# LCD_screen.net
KiCad netlist of a schematic drawn in Altium Designer
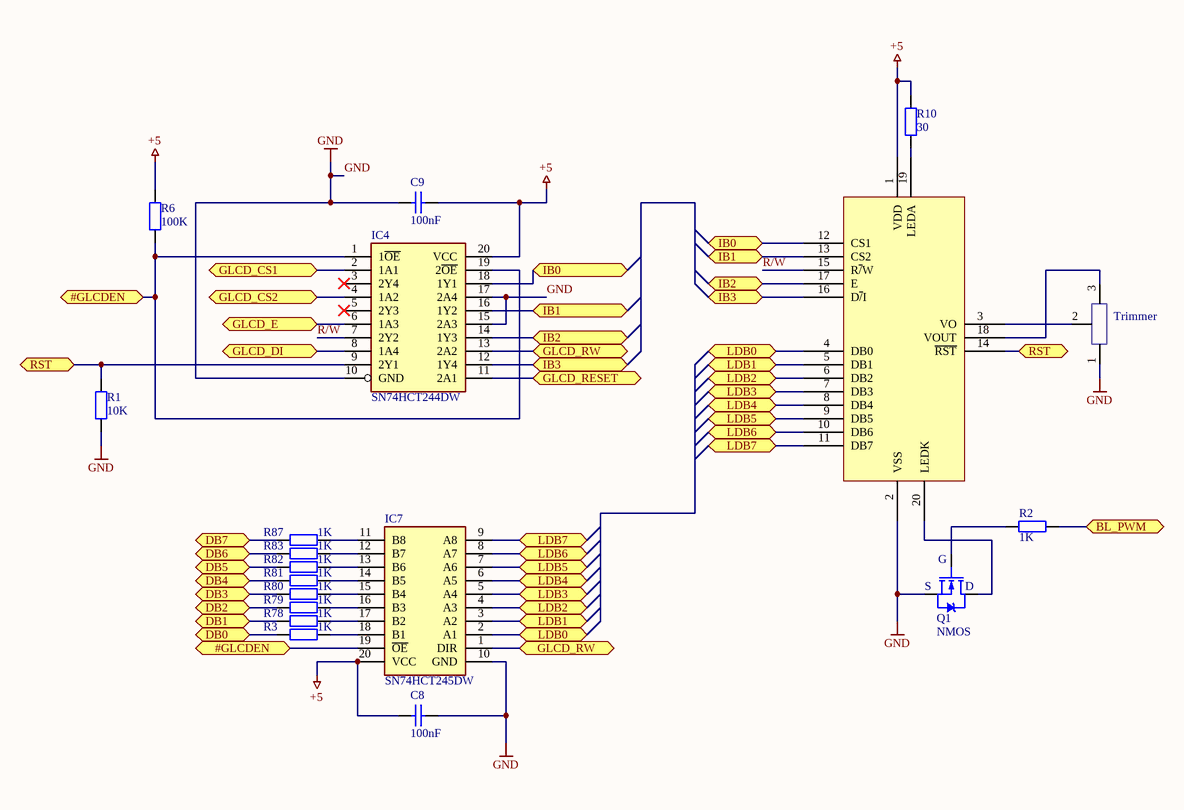
[diagram p0: LCD_screen.SchDoc]

(export (version "E")
  (design (tool "Eeschema 10.0.6"))
  (components
    (comp (ref "BC817")
      (value "LCD Screen")
      (footprint "FP_LCD")
      (libsource (lib "hallglib") (part "LCD Screen"))
    )
    (comp (ref "C8")
      (value "100nF")
      (footprint "FP_0805_CAP_085")
      (description "Capacitor")
      (libsource (lib "hallglib") (part "CAP"))
    )
    (comp (ref "C9")
      (value "100nF")
      (footprint "FP_0805_CAP_085")
      (description "Capacitor")
      (libsource (lib "hallglib") (part "CAP"))
    )
    (comp (ref "IC4")
      (value "SN74HCT244DW")
      (footprint "hallglib:SOIC127P1030X265-20N")
      (description "Integrated Circuit")
      (fields (field (name "MOUSER PART NUMBER") "595-SN74HCT244DW"))
      (libsource (lib "hallglib") (part "SN74HCT244DW"))
    )
    (comp (ref "IC7")
      (value "SN74HCT245DW")
      (footprint "hallglib:SOIC127P1030X265-20N")
      (description "Integrated Circuit")
      (fields (field (name "MOUSER PART NUMBER") "595-SN74HCT245DW"))
      (libsource (lib "hallglib") (part "SN74HCT245DW"))
    )
    (comp (ref "Q1")
      (value "NMOS")
      (footprint "FP_SOT23-3")
      (description "NXP - BSP030,115 - MOSFET, N CH, 30V, 10A, SOT223")
      (libsource (lib "hallglib") (part "NMOS"))
    )
    (comp (ref "R1")
      (value "10K")
      (footprint "FP_0805_RES")
      (description "Resistor")
      (libsource (lib "") (part "RES_1"))
    )
    (comp (ref "R2")
      (value "1K")
      (footprint "FP_0805_RES")
      (description "Resistor")
      (libsource (lib "hallglib") (part "RES"))
    )
    (comp (ref "R3")
      (value "1K")
      (footprint "FP_0805_RES")
      (description "Resistor")
      (libsource (lib "hallglib") (part "RES"))
    )
    (comp (ref "R6")
      (value "100K")
      (footprint "FP_0805_RES")
      (description "Resistor")
      (libsource (lib "") (part "RES_1"))
    )
    (comp (ref "R10")
      (value "30")
      (footprint "FP_0805_RES")
      (description "Resistor")
      (libsource (lib "") (part "RES_1"))
    )
    (comp (ref "R78")
      (value "1K")
      (footprint "FP_0805_RES")
      (description "Resistor")
      (libsource (lib "hallglib") (part "RES"))
    )
    (comp (ref "R79")
      (value "1K")
      (footprint "FP_0805_RES")
      (description "Resistor")
      (libsource (lib "hallglib") (part "RES"))
    )
    (comp (ref "R80")
      (value "1K")
      (footprint "FP_0805_RES")
      (description "Resistor")
      (libsource (lib "hallglib") (part "RES"))
    )
    (comp (ref "R81")
      (value "1K")
      (footprint "FP_0805_RES")
      (description "Resistor")
      (libsource (lib "hallglib") (part "RES"))
    )
    (comp (ref "R82")
      (value "1K")
      (footprint "FP_0805_RES")
      (description "Resistor")
      (libsource (lib "hallglib") (part "RES"))
    )
    (comp (ref "R83")
      (value "1K")
      (footprint "FP_0805_RES")
      (description "Resistor")
      (libsource (lib "hallglib") (part "RES"))
    )
    (comp (ref "R87")
      (value "1K")
      (footprint "FP_0805_RES")
      (description "Resistor")
      (libsource (lib "hallglib") (part "RES"))
    )
    (comp (ref "Trimmer")
      (value "~")
      (footprint "TRIM_3362P-1-502")
      (libsource (lib "hallglib") (part "Trimmer"))
    )
  )
  (nets
    (net (code "1") (name "+5") (class "Default")
      (node (ref "BC817") (pin "1") (pinfunction "VDD_1") (pintype "passive"))
      (node (ref "C8") (pin "1") (pinfunction "1_1") (pintype "passive"))
      (node (ref "C9") (pin "2") (pinfunction "2_2") (pintype "passive"))
      (node (ref "IC4") (pin "20") (pinfunction "VCC_20") (pintype "passive"))
      (node (ref "IC7") (pin "20") (pinfunction "VCC_20") (pintype "passive"))
      (node (ref "R10") (pin "2") (pinfunction "2_2") (pintype "passive"))
      (node (ref "R6") (pin "2") (pinfunction "2_2") (pintype "passive"))
    )
    (net (code "2") (name "/#GLCDEN") (class "Default")
      (node (ref "IC4") (pin "1") (pinfunction "1~{OE}_1") (pintype "passive"))
      (node (ref "IC4") (pin "19") (pinfunction "2~{OE}_19") (pintype "passive"))
      (node (ref "IC7") (pin "19") (pinfunction "~{OE}_19") (pintype "passive"))
      (node (ref "R6") (pin "1") (pinfunction "1_1") (pintype "passive"))
    )
    (net (code "3") (name "/BL_PWM") (class "Default")
      (node (ref "R2") (pin "2") (pinfunction "2_2") (pintype "passive"))
    )
    (net (code "4") (name "/DB0") (class "Default")
      (node (ref "R3") (pin "1") (pinfunction "1_1") (pintype "passive"))
    )
    (net (code "5") (name "/DB1") (class "Default")
      (node (ref "R78") (pin "1") (pinfunction "1_1") (pintype "passive"))
    )
    (net (code "6") (name "/DB2") (class "Default")
      (node (ref "R79") (pin "1") (pinfunction "1_1") (pintype "passive"))
    )
    (net (code "7") (name "/DB3") (class "Default")
      (node (ref "R80") (pin "1") (pinfunction "1_1") (pintype "passive"))
    )
    (net (code "8") (name "/DB4") (class "Default")
      (node (ref "R81") (pin "1") (pinfunction "1_1") (pintype "passive"))
    )
    (net (code "9") (name "/DB5") (class "Default")
      (node (ref "R82") (pin "1") (pinfunction "1_1") (pintype "passive"))
    )
    (net (code "10") (name "/DB6") (class "Default")
      (node (ref "R83") (pin "1") (pinfunction "1_1") (pintype "passive"))
    )
    (net (code "11") (name "/DB7") (class "Default")
      (node (ref "R87") (pin "1") (pinfunction "1_1") (pintype "passive"))
    )
    (net (code "12") (name "/GLCD_CS1") (class "Default")
      (node (ref "IC4") (pin "2") (pinfunction "1A1_2") (pintype "passive"))
    )
    (net (code "13") (name "/GLCD_CS2") (class "Default")
      (node (ref "IC4") (pin "4") (pinfunction "1A2_4") (pintype "passive"))
    )
    (net (code "14") (name "/GLCD_DI") (class "Default")
      (node (ref "IC4") (pin "8") (pinfunction "1A4_8") (pintype "passive"))
    )
    (net (code "15") (name "/GLCD_E") (class "Default")
      (node (ref "IC4") (pin "6") (pinfunction "1A3_6") (pintype "passive"))
    )
    (net (code "16") (name "/GLCD_RESET") (class "Default")
      (node (ref "IC4") (pin "11") (pinfunction "2A1_11") (pintype "passive"))
    )
    (net (code "17") (name "/GLCD_RW") (class "Default")
      (node (ref "IC4") (pin "13") (pinfunction "2A2_13") (pintype "passive"))
      (node (ref "IC7") (pin "1") (pinfunction "DIR_1") (pintype "passive"))
    )
    (net (code "18") (name "/IB0") (class "Default")
      (node (ref "BC817") (pin "12") (pinfunction "CS1_12") (pintype "passive"))
      (node (ref "IC4") (pin "18") (pinfunction "1Y1_18") (pintype "passive"))
    )
    (net (code "19") (name "/IB1") (class "Default")
      (node (ref "BC817") (pin "13") (pinfunction "CS2_13") (pintype "passive"))
      (node (ref "IC4") (pin "16") (pinfunction "1Y2_16") (pintype "passive"))
    )
    (net (code "20") (name "/IB2") (class "Default")
      (node (ref "BC817") (pin "17") (pinfunction "E_17") (pintype "passive"))
      (node (ref "IC4") (pin "14") (pinfunction "1Y3_14") (pintype "passive"))
    )
    (net (code "21") (name "/IB3") (class "Default")
      (node (ref "BC817") (pin "16") (pinfunction "D~{/}I_16") (pintype "passive"))
      (node (ref "IC4") (pin "12") (pinfunction "1Y4_12") (pintype "passive"))
    )
    (net (code "22") (name "/LDB0") (class "Default")
      (node (ref "BC817") (pin "4") (pinfunction "DB0_4") (pintype "passive"))
      (node (ref "IC7") (pin "2") (pinfunction "A1_2") (pintype "passive"))
    )
    (net (code "23") (name "/LDB1") (class "Default")
      (node (ref "BC817") (pin "5") (pinfunction "DB1_5") (pintype "passive"))
      (node (ref "IC7") (pin "3") (pinfunction "A2_3") (pintype "passive"))
    )
    (net (code "24") (name "/LDB2") (class "Default")
      (node (ref "BC817") (pin "6") (pinfunction "DB2_6") (pintype "passive"))
      (node (ref "IC7") (pin "4") (pinfunction "A3_4") (pintype "passive"))
    )
    (net (code "25") (name "/LDB3") (class "Default")
      (node (ref "BC817") (pin "7") (pinfunction "DB3_7") (pintype "passive"))
      (node (ref "IC7") (pin "5") (pinfunction "A4_5") (pintype "passive"))
    )
    (net (code "26") (name "/LDB4") (class "Default")
      (node (ref "BC817") (pin "8") (pinfunction "DB4_8") (pintype "passive"))
      (node (ref "IC7") (pin "6") (pinfunction "A5_6") (pintype "passive"))
    )
    (net (code "27") (name "/LDB5") (class "Default")
      (node (ref "BC817") (pin "9") (pinfunction "DB5_9") (pintype "passive"))
      (node (ref "IC7") (pin "7") (pinfunction "A6_7") (pintype "passive"))
    )
    (net (code "28") (name "/LDB6") (class "Default")
      (node (ref "BC817") (pin "10") (pinfunction "DB6_10") (pintype "passive"))
      (node (ref "IC7") (pin "8") (pinfunction "A7_8") (pintype "passive"))
    )
    (net (code "29") (name "/LDB7") (class "Default")
      (node (ref "BC817") (pin "11") (pinfunction "DB7_11") (pintype "passive"))
      (node (ref "IC7") (pin "9") (pinfunction "A8_9") (pintype "passive"))
    )
    (net (code "30") (name "/RST") (class "Default")
      (node (ref "BC817") (pin "14") (pinfunction "RST_14") (pintype "passive"))
      (node (ref "IC4") (pin "9") (pinfunction "2Y1_9") (pintype "passive"))
      (node (ref "R1") (pin "2") (pinfunction "2_2") (pintype "passive"))
    )
    (net (code "31") (name "/R{slash}W") (class "Default")
      (node (ref "BC817") (pin "15") (pinfunction "R~{/}W_15") (pintype "passive"))
      (node (ref "IC4") (pin "7") (pinfunction "2Y2_7") (pintype "passive"))
    )
    (net (code "32") (name "GND") (class "Default")
      (node (ref "BC817") (pin "2") (pinfunction "VSS_2") (pintype "passive"))
      (node (ref "C8") (pin "2") (pinfunction "2_2") (pintype "passive"))
      (node (ref "C9") (pin "1") (pinfunction "1_1") (pintype "passive"))
      (node (ref "IC4") (pin "10") (pinfunction "GND_10") (pintype "passive"))
      (node (ref "IC4") (pin "15") (pinfunction "2A3_15") (pintype "passive"))
      (node (ref "IC4") (pin "17") (pinfunction "2A4_17") (pintype "passive"))
      (node (ref "IC7") (pin "10") (pinfunction "GND_10") (pintype "passive"))
      (node (ref "Q1") (pin "3") (pinfunction "S_3") (pintype "passive"))
      (node (ref "R1") (pin "1") (pinfunction "1_1") (pintype "passive"))
      (node (ref "Trimmer") (pin "1") (pintype "passive"))
    )
    (net (code "33") (name "Net-(BC817-LEDA)") (class "Default")
      (node (ref "BC817") (pin "19") (pinfunction "LEDA_19") (pintype "passive"))
      (node (ref "R10") (pin "1") (pinfunction "1_1") (pintype "passive"))
    )
    (net (code "34") (name "Net-(BC817-LEDK)") (class "Default")
      (node (ref "BC817") (pin "20") (pinfunction "LEDK_20") (pintype "passive"))
      (node (ref "Q1") (pin "2") (pinfunction "D_2") (pintype "passive"))
    )
    (net (code "35") (name "Net-(BC817-VO)") (class "Default")
      (node (ref "BC817") (pin "3") (pinfunction "VO_3") (pintype "passive"))
      (node (ref "Trimmer") (pin "2") (pintype "passive"))
    )
    (net (code "36") (name "Net-(BC817-VOUT)") (class "Default")
      (node (ref "BC817") (pin "18") (pinfunction "VOUT_18") (pintype "passive"))
      (node (ref "Trimmer") (pin "3") (pintype "passive"))
    )
    (net (code "37") (name "Net-(IC7-B1)") (class "Default")
      (node (ref "IC7") (pin "18") (pinfunction "B1_18") (pintype "passive"))
      (node (ref "R3") (pin "2") (pinfunction "2_2") (pintype "passive"))
    )
    (net (code "38") (name "Net-(IC7-B2)") (class "Default")
      (node (ref "IC7") (pin "17") (pinfunction "B2_17") (pintype "passive"))
      (node (ref "R78") (pin "2") (pinfunction "2_2") (pintype "passive"))
    )
    (net (code "39") (name "Net-(IC7-B3)") (class "Default")
      (node (ref "IC7") (pin "16") (pinfunction "B3_16") (pintype "passive"))
      (node (ref "R79") (pin "2") (pinfunction "2_2") (pintype "passive"))
    )
    (net (code "40") (name "Net-(IC7-B4)") (class "Default")
      (node (ref "IC7") (pin "15") (pinfunction "B4_15") (pintype "passive"))
      (node (ref "R80") (pin "2") (pinfunction "2_2") (pintype "passive"))
    )
    (net (code "41") (name "Net-(IC7-B5)") (class "Default")
      (node (ref "IC7") (pin "14") (pinfunction "B5_14") (pintype "passive"))
      (node (ref "R81") (pin "2") (pinfunction "2_2") (pintype "passive"))
    )
    (net (code "42") (name "Net-(IC7-B6)") (class "Default")
      (node (ref "IC7") (pin "13") (pinfunction "B6_13") (pintype "passive"))
      (node (ref "R82") (pin "2") (pinfunction "2_2") (pintype "passive"))
    )
    (net (code "43") (name "Net-(IC7-B7)") (class "Default")
      (node (ref "IC7") (pin "12") (pinfunction "B7_12") (pintype "passive"))
      (node (ref "R83") (pin "2") (pinfunction "2_2") (pintype "passive"))
    )
    (net (code "44") (name "Net-(IC7-B8)") (class "Default")
      (node (ref "IC7") (pin "11") (pinfunction "B8_11") (pintype "passive"))
      (node (ref "R87") (pin "2") (pinfunction "2_2") (pintype "passive"))
    )
    (net (code "45") (name "Net-(Q1-G)") (class "Default")
      (node (ref "Q1") (pin "1") (pinfunction "G_1") (pintype "passive"))
      (node (ref "R2") (pin "1") (pinfunction "1_1") (pintype "passive"))
    )
    (net (code "46") (name "unconnected-(IC4-2Y3-Pad5)") (class "Default")
      (node (ref "IC4") (pin "5") (pinfunction "2Y3_5") (pintype "passive+no_connect"))
    )
    (net (code "47") (name "unconnected-(IC4-2Y4-Pad3)") (class "Default")
      (node (ref "IC4") (pin "3") (pinfunction "2Y4_3") (pintype "passive+no_connect"))
    )
  )
)
